# ChopperAmp.net
KiCad netlist of a schematic drawn in Altium Designer
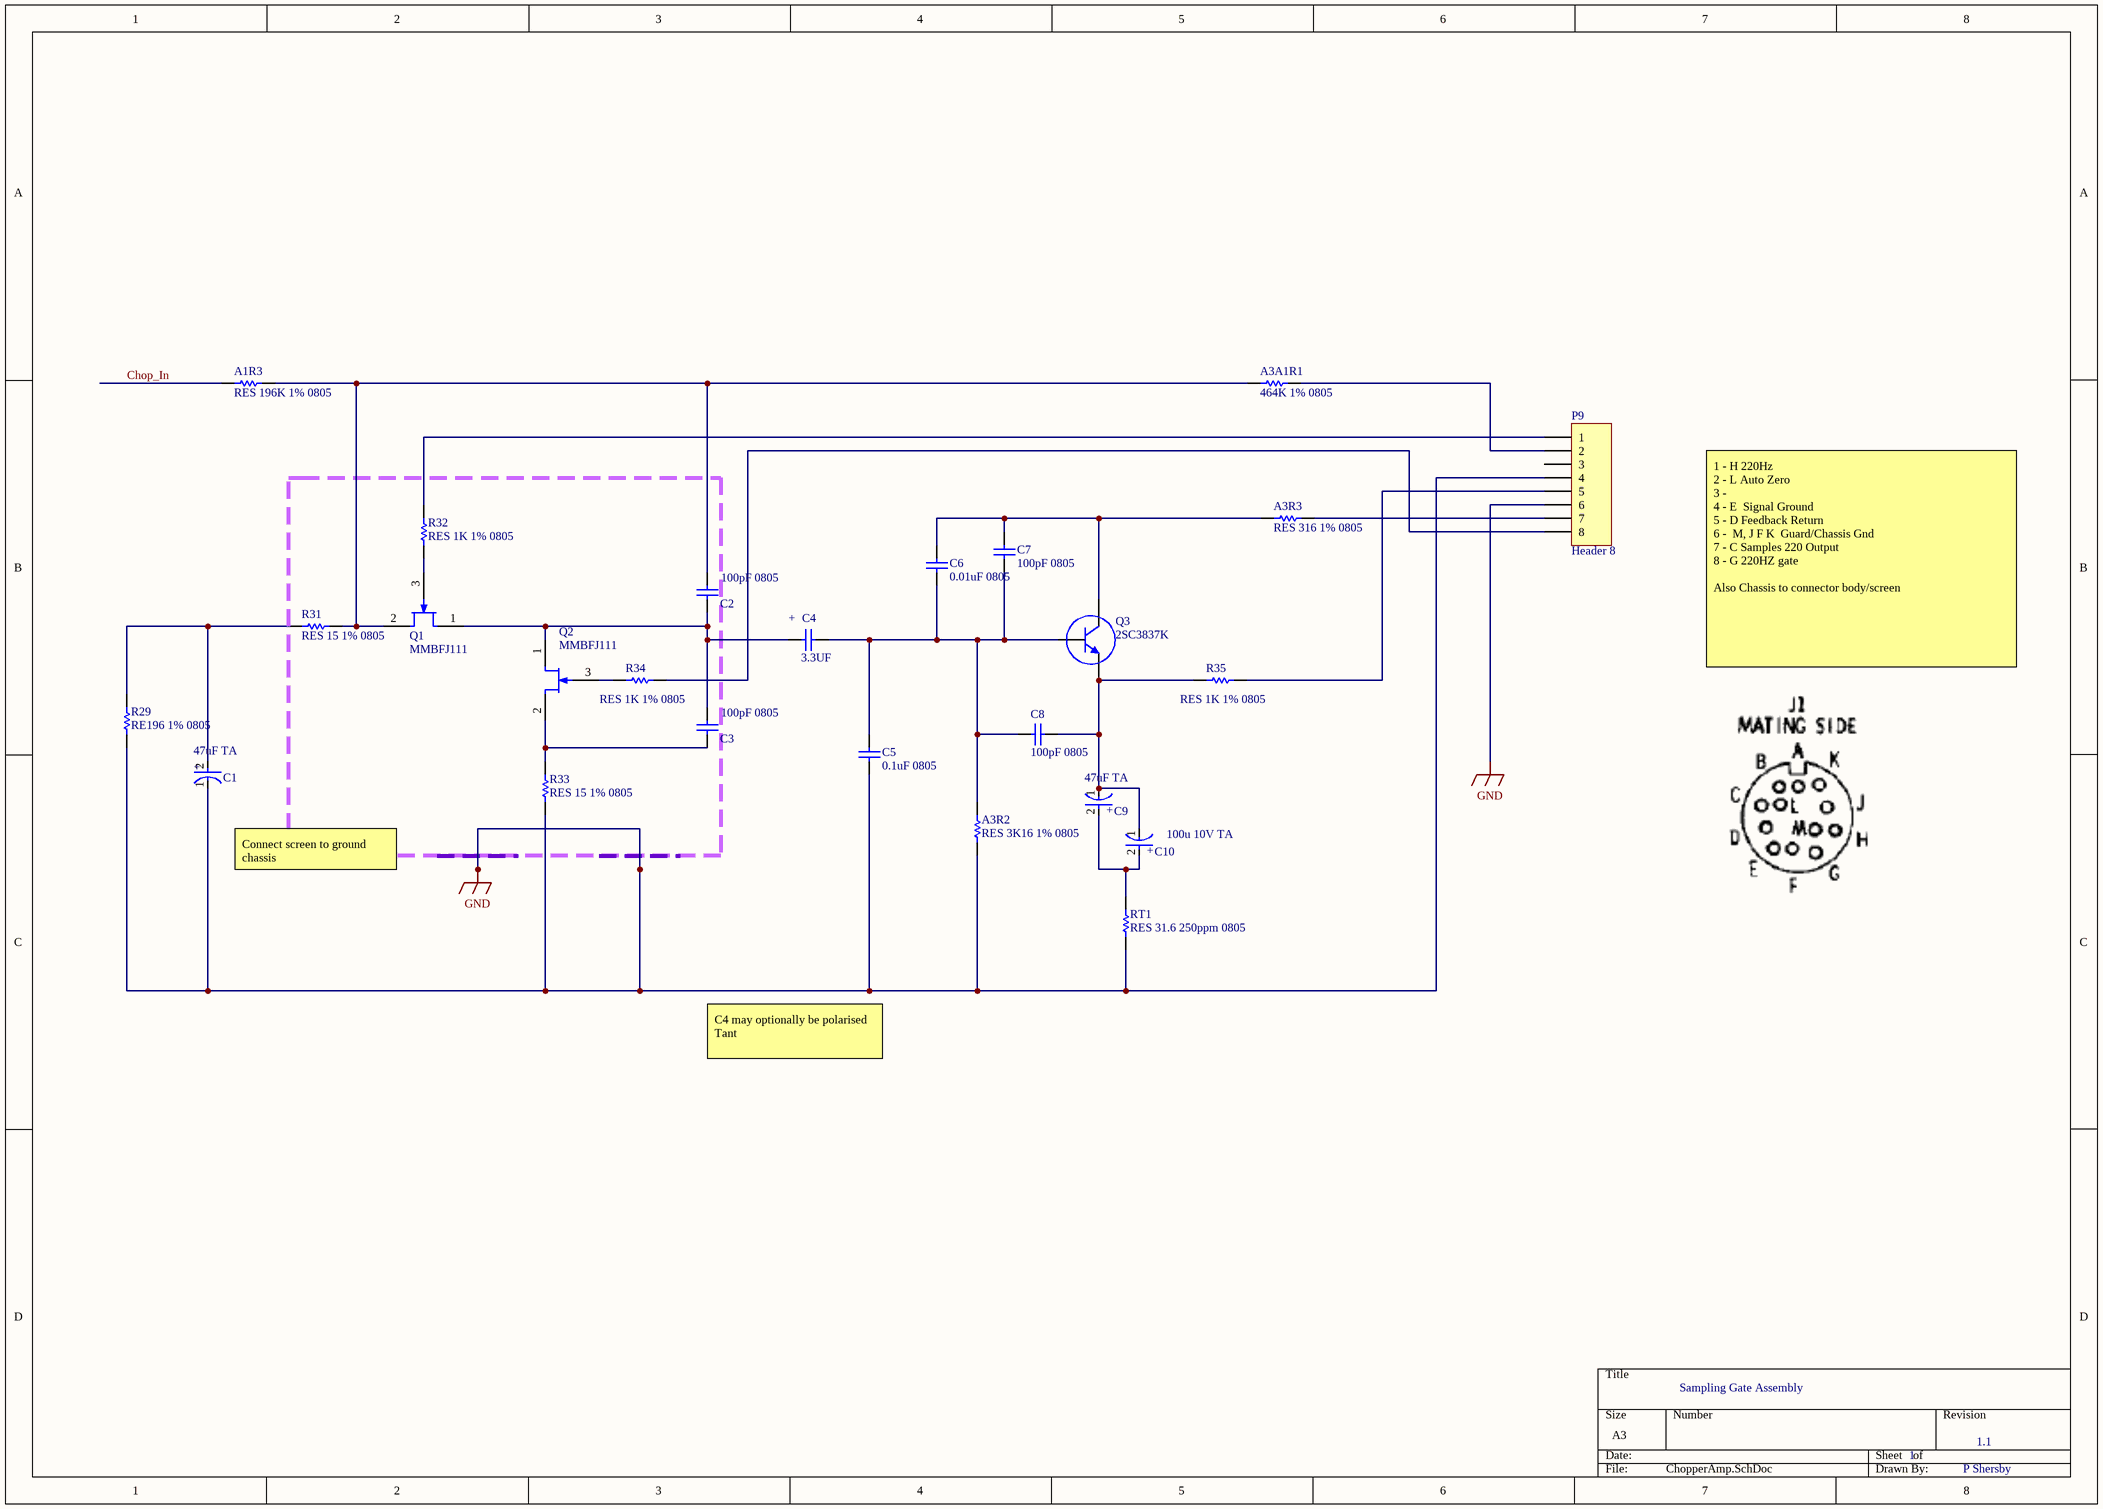
[diagram p0: ChopperAmp.SchDoc]

(export (version "E")
  (design (tool "Eeschema 10.0.6"))
  (components
    (comp (ref "A1R3")
      (value "RES 196K 1% 0805")
      (footprint "RESC2013X70X40LL20T20")
      (description "Resistor 196K 1% 0805  1/8W 10ppm/C")
      (fields (field (name "MANUFACTURER") "Panasonic"))
      (libsource (lib "Altium Content Vault") (part "CMP-2001-00110-5"))
    )
    (comp (ref "A3A1R1")
      (value "464K 1% 0805")
      (footprint "RESC2013X70X40LL20T20")
      (description "Resistor 464K 1% 0805   0.2W 10ppm/C")
      (fields (field (name "MANUFACTURER") "Panasonic"))
      (libsource (lib "Altium Content Vault") (part "CMP-2001-00110-5"))
    )
    (comp (ref "A3R2")
      (value "RES 3K16 1% 0805")
      (footprint "RESC2013X70X40LL20T20")
      (description "Resistor 3K!6 1% 0805  1/8W 10ppm/C")
      (fields (field (name "MANUFACTURER") "Panasonic"))
      (libsource (lib "Altium Content Vault") (part "CMP-2001-00110-5"))
    )
    (comp (ref "A3R3")
      (value "RES 316 1% 0805")
      (footprint "RESC2013X70X40LL20T20")
      (description "Resistor 316 1% 0805  1/8W 10ppm/C")
      (fields (field (name "MANUFACTURER") "Panasonic"))
      (libsource (lib "Altium Content Vault") (part "CMP-2001-00110-5"))
    )
    (comp (ref "C1")
      (value "47uF TA")
      (footprint "FP-TAJB-MFG")
      (description "47uF Tant 4V 1411")
      (fields
        (field (name "MANUFACTURER") "AVX Corporation")
        (field (name "MANUFACTURER PART NUMBER") "TAJB475K010RNJ")
      )
      (libsource (lib "Altium Content Vault") (part "CMP-04424-000035-1"))
    )
    (comp (ref "C2")
      (value "100pF 0805")
      (footprint "CAPC2113X88X50NL30T25")
      (fields (field (name "MANUFACTURER") "Kemet") (field (name "PART NUMBER") "C0805X474K4RACTU"))
      (libsource (lib "Altium Content Vault") (part "CMP-2007-00001-1"))
    )
    (comp (ref "C3")
      (value "100pF 0805")
      (footprint "CAPC2113X88X50NL30T25")
      (fields (field (name "MANUFACTURER") "Kemet") (field (name "PART NUMBER") "C0805X474K4RACTU"))
      (libsource (lib "Altium Content Vault") (part "CMP-2007-00001-1"))
    )
    (comp (ref "C4")
      (value "3.3UF")
      (footprint "CAPC1206(3216)150_L")
      (description "1206 (3216 Metric) Chip Capacitor")
      (libsource (lib "Altium Content Vault") (part "CMP-1590-00001-1"))
    )
    (comp (ref "C5")
      (value "0.1uF 0805")
      (footprint "CAPC2113X88X50NL30T25")
      (fields (field (name "MANUFACTURER") "Kemet") (field (name "PART NUMBER") "C0805X474K4RACTU"))
      (libsource (lib "Altium Content Vault") (part "CMP-2007-00001-1"))
    )
    (comp (ref "C6")
      (value "0.01uF 0805")
      (footprint "CAPC2113X88X50NL30T25")
      (fields (field (name "MANUFACTURER") "Kemet") (field (name "PART NUMBER") "C0805X474K4RACTU"))
      (libsource (lib "Altium Content Vault") (part "CMP-2007-00001-1"))
    )
    (comp (ref "C7")
      (value "100pF 0805")
      (footprint "CAPC2113X88X50NL30T25")
      (fields (field (name "MANUFACTURER") "Kemet") (field (name "PART NUMBER") "C0805X474K4RACTU"))
      (libsource (lib "Altium Content Vault") (part "CMP-2007-00001-1"))
    )
    (comp (ref "C8")
      (value "100pF 0805")
      (footprint "CAPC2113X88X50NL30T25")
      (fields (field (name "MANUFACTURER") "Kemet") (field (name "PART NUMBER") "C0805X474K4RACTU"))
      (libsource (lib "Altium Content Vault") (part "CMP-2007-00001-1"))
    )
    (comp (ref "C9")
      (value "47uF TA")
      (footprint "FP-TAJB-MFG")
      (description "47uF Tant 4V 1411")
      (fields
        (field (name "MANUFACTURER") "AVX Corporation")
        (field (name "MANUFACTURER PART NUMBER") "TAJB475K010RNJ")
      )
      (libsource (lib "Altium Content Vault") (part "CMP-04424-000035-1"))
    )
    (comp (ref "C10")
      (value "100u 10V TA")
      (footprint "FP-TPE-D4-MFG")
      (description "CAP TANT 100u 10V")
      (fields (field (name "TOLERANCE") "20%") (field (name "MANUFACTURER PART NUMBER") "6TPE330MAA"))
      (libsource (lib "Altium Content Vault") (part "CMP-05428-000010-1"))
    )
    (comp (ref "P9")
      (value "Header 8")
      (footprint "HDR1X8")
      (description "Header, 8-Pin")
      (fields (field (name "PUBLISHER") "Altium Limited"))
      (libsource (lib "Miscellaneous Connectors") (part "Header 8"))
    )
    (comp (ref "Q1")
      (value "MMBFJ111")
      (footprint "ONSC-SOT-23-3-318-08_V")
      (description "JFET - VHF / UJFET Chopper")
      (fields (field (name "PARTNUMBER") "MMBFJ310LT3") (field (name "MANUFACTURER") "On Semiconductor"))
      (libsource (lib "Altium Content Vault") (part "CMP-1062-00038-1"))
    )
    (comp (ref "Q2")
      (value "MMBFJ111")
      (footprint "ONSC-SOT-23-3-318-08_V")
      (description "JFET - VHF / UJFET Chopper")
      (fields (field (name "PARTNUMBER") "MMBFJ310LT3") (field (name "MANUFACTURER") "On Semiconductor"))
      (libsource (lib "Altium Content Vault") (part "CMP-1062-00038-1"))
    )
    (comp (ref "Q3") (value "2SC3837K") (footprint "SC-59") (libsource (lib "Discrete Semi") (part "NPN")))
    (comp (ref "R29")
      (value "RE196 1% 0805")
      (footprint "RESC2013X70X40LL20T20")
      (description "Resistor 196 1% 0805  0.2W 10ppm/C")
      (fields (field (name "MANUFACTURER") "Panasonic"))
      (libsource (lib "Altium Content Vault") (part "CMP-2001-00110-5"))
    )
    (comp (ref "R31")
      (value "RES 15 1% 0805")
      (footprint "RESC2013X70X40LL20T20")
      (description "Resistor 15 1% 0805  0.2W 10ppm/C")
      (fields (field (name "MANUFACTURER") "Panasonic"))
      (libsource (lib "Altium Content Vault") (part "CMP-2001-00110-5"))
    )
    (comp (ref "R32")
      (value "RES 1K 1% 0805")
      (footprint "RESC2013X70X40LL20T20")
      (description "Resistor 1K 1% 0805  0.2W 10ppm/C")
      (fields (field (name "MANUFACTURER") "Panasonic"))
      (libsource (lib "Altium Content Vault") (part "CMP-2001-00110-5"))
    )
    (comp (ref "R33")
      (value "RES 15 1% 0805")
      (footprint "RESC2013X70X40LL20T20")
      (description "Resistor 15 1% 0805  0.2W 10ppm/C")
      (fields (field (name "MANUFACTURER") "Panasonic"))
      (libsource (lib "Altium Content Vault") (part "CMP-2001-00110-5"))
    )
    (comp (ref "R34")
      (value "RES 1K 1% 0805")
      (footprint "RESC2013X70X40LL20T20")
      (description "Resistor 1K1% 0805  0.2W 10ppm/C")
      (fields (field (name "MANUFACTURER") "Panasonic"))
      (libsource (lib "Altium Content Vault") (part "CMP-2001-00110-5"))
    )
    (comp (ref "R35")
      (value "RES 1K 1% 0805")
      (footprint "RESC2013X70X40LL20T20")
      (description "Resistor 1K1% 0805  0.2W 10ppm/C")
      (fields (field (name "MANUFACTURER") "Panasonic"))
      (libsource (lib "Altium Content Vault") (part "CMP-2001-00110-5"))
    )
    (comp (ref "RT1")
      (value "RES 31.6 250ppm 0805")
      (footprint "RESC2013X70X40LL20T20")
      (fields (field (name "MANUFACTURER") "Panasonic"))
      (libsource (lib "Altium Content Vault") (part "CMP-2001-00110-5"))
    )
    (comp (ref "SC1")
      (value "ScreenConnection")
      (footprint "ScreenConnection")
      (libsource (lib "Mechanical") (part "ScreenConnection"))
    )
    (comp (ref "SC2")
      (value "ScreenConnection")
      (footprint "ScreenConnection")
      (libsource (lib "Mechanical") (part "ScreenConnection"))
    )
  )
  (nets
    (net (code "1") (name "/Chop_In") (class "Default")
      (node (ref "A1R3") (pin "1") (pinfunction "1_1") (pintype "passive"))
    )
    (net (code "2") (name "GND") (class "Default")
      (node (ref "A3R2") (pin "1") (pinfunction "1_1") (pintype "passive"))
      (node (ref "C1") (pin "1") (pinfunction "C_1") (pintype "passive"))
      (node (ref "C5") (pin "2") (pinfunction "2_2") (pintype "passive"))
      (node (ref "P9") (pin "4") (pinfunction "4_4") (pintype "passive"))
      (node (ref "P9") (pin "6") (pinfunction "6_6") (pintype "passive"))
      (node (ref "R29") (pin "2") (pinfunction "2_2") (pintype "passive"))
      (node (ref "R33") (pin "2") (pinfunction "2_2") (pintype "passive"))
      (node (ref "RT1") (pin "1") (pinfunction "1_1") (pintype "passive"))
      (node (ref "SC1") (pin "1") (pinfunction "1_1") (pintype "passive"))
      (node (ref "SC2") (pin "1") (pinfunction "1_1") (pintype "passive"))
    )
    (net (code "3") (name "Net-(A3A1R1-Pad2)") (class "Default")
      (node (ref "A3A1R1") (pin "2") (pinfunction "2_2") (pintype "passive"))
      (node (ref "P9") (pin "2") (pinfunction "2_2") (pintype "passive"))
    )
    (net (code "4") (name "Net-(A3R3-Pad2)") (class "Default")
      (node (ref "A3R3") (pin "2") (pinfunction "2_2") (pintype "passive"))
      (node (ref "P9") (pin "7") (pinfunction "7_7") (pintype "passive"))
    )
    (net (code "5") (name "Net-(C1-A)") (class "Default")
      (node (ref "C1") (pin "2") (pinfunction "A_2") (pintype "passive"))
      (node (ref "R29") (pin "1") (pinfunction "1_1") (pintype "passive"))
      (node (ref "R31") (pin "2") (pinfunction "2_2") (pintype "passive"))
    )
    (net (code "6") (name "Net-(C10-A)") (class "Default")
      (node (ref "C10") (pin "2") (pinfunction "A_2") (pintype "passive"))
      (node (ref "C9") (pin "2") (pinfunction "A_2") (pintype "passive"))
      (node (ref "RT1") (pin "2") (pinfunction "2_2") (pintype "passive"))
    )
    (net (code "7") (name "Net-(C10-C)") (class "Default")
      (node (ref "C10") (pin "1") (pinfunction "C_1") (pintype "passive"))
      (node (ref "C8") (pin "1") (pinfunction "1_1") (pintype "passive"))
      (node (ref "C9") (pin "1") (pinfunction "C_1") (pintype "passive"))
      (node (ref "Q3") (pin "3") (pinfunction "E_3") (pintype "passive"))
      (node (ref "R35") (pin "1") (pinfunction "1_1") (pintype "passive"))
    )
    (net (code "8") (name "Net-(P9-Pad1)") (class "Default")
      (node (ref "P9") (pin "1") (pinfunction "1_1") (pintype "passive"))
      (node (ref "R32") (pin "1") (pinfunction "1_1") (pintype "passive"))
    )
    (net (code "9") (name "Net-(P9-Pad5)") (class "Default")
      (node (ref "P9") (pin "5") (pinfunction "5_5") (pintype "passive"))
      (node (ref "R35") (pin "2") (pinfunction "2_2") (pintype "passive"))
    )
    (net (code "10") (name "Net-(P9-Pad8)") (class "Default")
      (node (ref "P9") (pin "8") (pinfunction "8_8") (pintype "passive"))
      (node (ref "R34") (pin "2") (pinfunction "2_2") (pintype "passive"))
    )
    (net (code "11") (name "Net-(Q1-D)") (class "Default")
      (node (ref "C2") (pin "1") (pinfunction "1_1") (pintype "passive"))
      (node (ref "C3") (pin "2") (pinfunction "2_2") (pintype "passive"))
      (node (ref "C4") (pin "1") (pinfunction "1_1") (pintype "passive"))
      (node (ref "Q1") (pin "1") (pinfunction "D_1") (pintype "passive"))
      (node (ref "Q2") (pin "1") (pinfunction "D_1") (pintype "passive"))
    )
    (net (code "12") (name "Net-(Q1-G)") (class "Default")
      (node (ref "Q1") (pin "3") (pinfunction "G_3") (pintype "passive"))
      (node (ref "R32") (pin "2") (pinfunction "2_2") (pintype "passive"))
    )
    (net (code "13") (name "Net-(Q1-S)") (class "Default")
      (node (ref "A1R3") (pin "2") (pinfunction "2_2") (pintype "passive"))
      (node (ref "A3A1R1") (pin "1") (pinfunction "1_1") (pintype "passive"))
      (node (ref "C2") (pin "2") (pinfunction "2_2") (pintype "passive"))
      (node (ref "Q1") (pin "2") (pinfunction "S_2") (pintype "passive"))
      (node (ref "R31") (pin "1") (pinfunction "1_1") (pintype "passive"))
    )
    (net (code "14") (name "Net-(Q2-G)") (class "Default")
      (node (ref "Q2") (pin "3") (pinfunction "G_3") (pintype "passive"))
      (node (ref "R34") (pin "1") (pinfunction "1_1") (pintype "passive"))
    )
    (net (code "15") (name "Net-(Q2-S)") (class "Default")
      (node (ref "C3") (pin "1") (pinfunction "1_1") (pintype "passive"))
      (node (ref "Q2") (pin "2") (pinfunction "S_2") (pintype "passive"))
      (node (ref "R33") (pin "1") (pinfunction "1_1") (pintype "passive"))
    )
    (net (code "16") (name "Net-(Q3-B)") (class "Default")
      (node (ref "A3R2") (pin "2") (pinfunction "2_2") (pintype "passive"))
      (node (ref "C4") (pin "2") (pinfunction "2_2") (pintype "passive"))
      (node (ref "C5") (pin "1") (pinfunction "1_1") (pintype "passive"))
      (node (ref "C6") (pin "2") (pinfunction "2_2") (pintype "passive"))
      (node (ref "C7") (pin "2") (pinfunction "2_2") (pintype "passive"))
      (node (ref "C8") (pin "2") (pinfunction "2_2") (pintype "passive"))
      (node (ref "Q3") (pin "2") (pinfunction "B_2") (pintype "passive"))
    )
    (net (code "17") (name "Net-(Q3-C)") (class "Default")
      (node (ref "A3R3") (pin "1") (pinfunction "1_1") (pintype "passive"))
      (node (ref "C6") (pin "1") (pinfunction "1_1") (pintype "passive"))
      (node (ref "C7") (pin "1") (pinfunction "1_1") (pintype "passive"))
      (node (ref "Q3") (pin "1") (pinfunction "C_1") (pintype "passive"))
    )
    (net (code "18") (name "unconnected-(P9-Pad3)") (class "Default")
      (node (ref "P9") (pin "3") (pinfunction "3_3") (pintype "passive"))
    )
  )
)
